# BM83_board.net
KiCad netlist of a schematic drawn in EAGLE
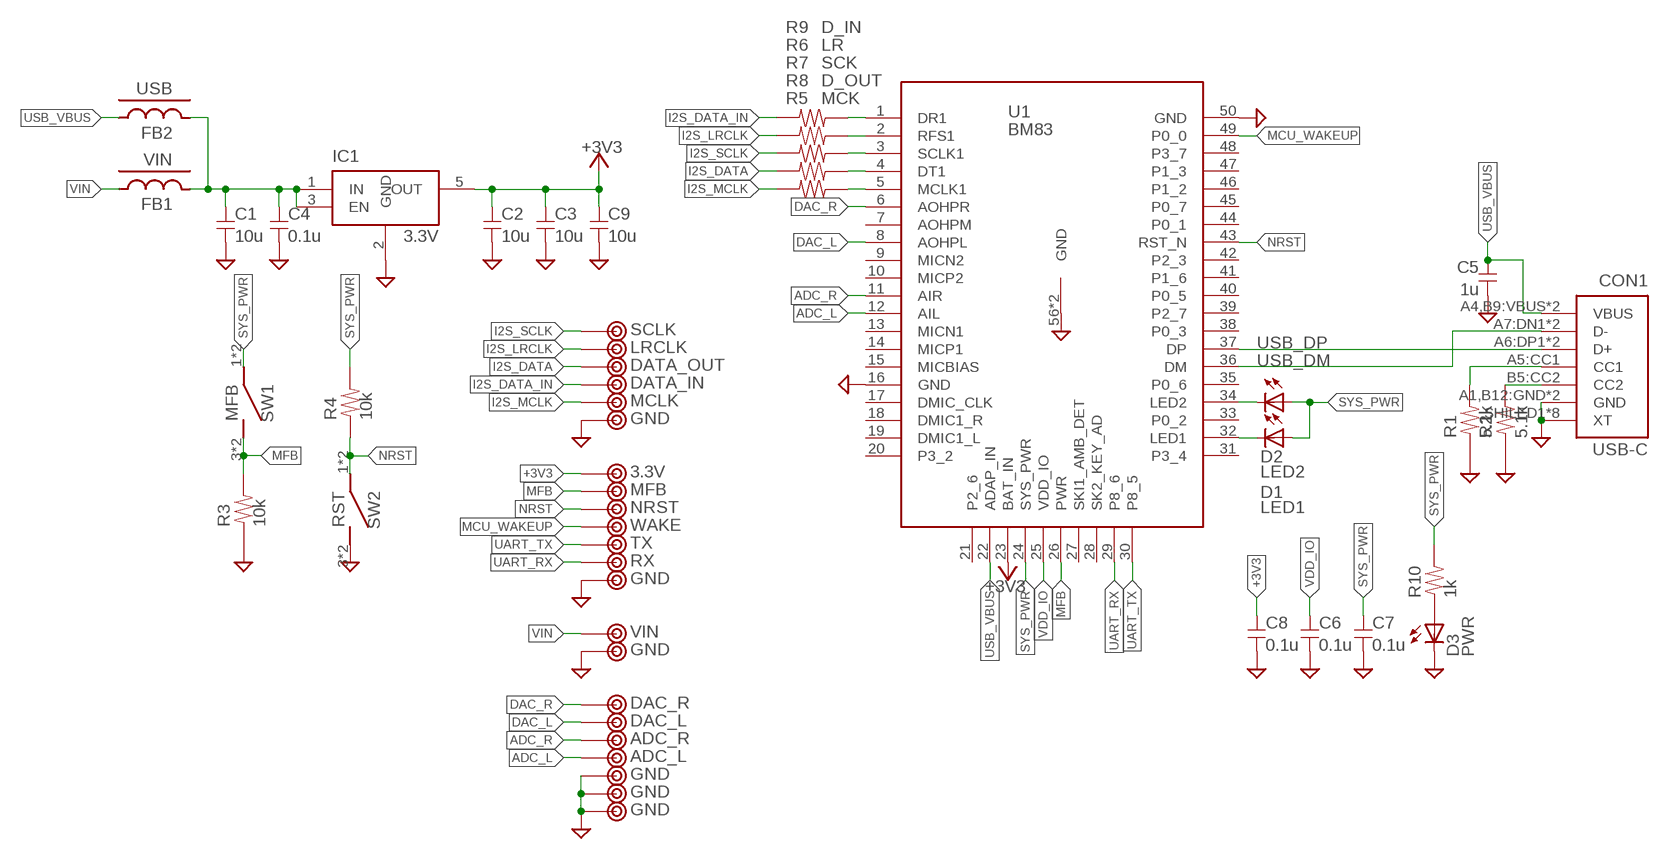
[diagram p0: schematic, sheet 1]

(export (version "E")
  (design (tool "Eeschema 10.0.6"))
  (components
    (comp (ref "C1")
      (value "10u")
      (footprint "eagle-import:2012")
      (libsource (lib "eagle-import") (part "C-2012"))
    )
    (comp (ref "C2")
      (value "10u")
      (footprint "eagle-import:2012")
      (libsource (lib "eagle-import") (part "C-2012"))
    )
    (comp (ref "C3")
      (value "10u")
      (footprint "eagle-import:2012")
      (libsource (lib "eagle-import") (part "C-2012"))
    )
    (comp (ref "C4")
      (value "0.1u")
      (footprint "eagle-import:1608C")
      (libsource (lib "eagle-import") (part "C-1608"))
    )
    (comp (ref "C5")
      (value "1u")
      (footprint "eagle-import:1608C")
      (libsource (lib "eagle-import") (part "C-1608"))
    )
    (comp (ref "C6")
      (value "0.1u")
      (footprint "eagle-import:1608C")
      (libsource (lib "eagle-import") (part "C-1608"))
    )
    (comp (ref "C7")
      (value "0.1u")
      (footprint "eagle-import:1608C")
      (libsource (lib "eagle-import") (part "C-1608"))
    )
    (comp (ref "C8")
      (value "0.1u")
      (footprint "eagle-import:1608C")
      (libsource (lib "eagle-import") (part "C-1608"))
    )
    (comp (ref "C9")
      (value "10u")
      (footprint "eagle-import:2012")
      (libsource (lib "eagle-import") (part "C-2012"))
    )
    (comp (ref "CON1")
      (value "USB-C")
      (footprint "eagle-import:5077CR-16-SMC2-BK-TR")
      (libsource (lib "eagle-import") (part "USB-C"))
    )
    (comp (ref "D1")
      (value "LED1")
      (footprint "eagle-import:D1608")
      (libsource (lib "eagle-import") (part "LED-SMD1608"))
    )
    (comp (ref "D2")
      (value "LED2")
      (footprint "eagle-import:D1608")
      (libsource (lib "eagle-import") (part "LED-SMD1608"))
    )
    (comp (ref "D3")
      (value "PWR")
      (footprint "eagle-import:D1608")
      (libsource (lib "eagle-import") (part "LED-SMD1608"))
    )
    (comp (ref "FB1")
      (value "VIN")
      (footprint "eagle-import:1608-FB")
      (libsource (lib "eagle-import") (part "FB-1608FB"))
    )
    (comp (ref "FB2")
      (value "USB")
      (footprint "eagle-import:1608-FB")
      (libsource (lib "eagle-import") (part "FB-1608FB"))
    )
    (comp (ref "IC1")
      (value "3.3V")
      (footprint "eagle-import:SOT23-5")
      (libsource (lib "eagle-import") (part "TLV740"))
    )
    (comp (ref "R1")
      (value "5.1k")
      (footprint "eagle-import:1608")
      (libsource (lib "eagle-import") (part "R-1608"))
    )
    (comp (ref "R2")
      (value "5.1k")
      (footprint "eagle-import:1608")
      (libsource (lib "eagle-import") (part "R-1608"))
    )
    (comp (ref "R3")
      (value "10k")
      (footprint "eagle-import:1608")
      (libsource (lib "eagle-import") (part "R-1608"))
    )
    (comp (ref "R4")
      (value "10k")
      (footprint "eagle-import:1608")
      (libsource (lib "eagle-import") (part "R-1608"))
    )
    (comp (ref "R5")
      (value "MCK")
      (footprint "eagle-import:1608-2")
      (libsource (lib "eagle-import") (part "R-1608-2"))
    )
    (comp (ref "R6")
      (value "LR")
      (footprint "eagle-import:1608-2")
      (libsource (lib "eagle-import") (part "R-1608-2"))
    )
    (comp (ref "R7")
      (value "SCK")
      (footprint "eagle-import:1608-2")
      (libsource (lib "eagle-import") (part "R-1608-2"))
    )
    (comp (ref "R8")
      (value "D_OUT")
      (footprint "eagle-import:1608-2")
      (libsource (lib "eagle-import") (part "R-1608-2"))
    )
    (comp (ref "R9")
      (value "D_IN")
      (footprint "eagle-import:1608-2")
      (libsource (lib "eagle-import") (part "R-1608-2"))
    )
    (comp (ref "R10")
      (value "1k")
      (footprint "eagle-import:1608")
      (libsource (lib "eagle-import") (part "R-1608"))
    )
    (comp (ref "SW1")
      (value "MFB")
      (footprint "eagle-import:SKRPACE010")
      (libsource (lib "eagle-import") (part "SW-SMD"))
    )
    (comp (ref "SW2")
      (value "RST")
      (footprint "eagle-import:SKRPACE010")
      (libsource (lib "eagle-import") (part "SW-SMD"))
    )
    (comp (ref "TP1")
      (value "DAC_R")
      (footprint "eagle-import:TESTPIN")
      (libsource (lib "eagle-import") (part "TESTPIN"))
    )
    (comp (ref "TP2")
      (value "DAC_L")
      (footprint "eagle-import:TESTPIN")
      (libsource (lib "eagle-import") (part "TESTPIN"))
    )
    (comp (ref "TP3")
      (value "GND")
      (footprint "eagle-import:TESTPIN")
      (libsource (lib "eagle-import") (part "TESTPIN"))
    )
    (comp (ref "TP4")
      (value "SCLK")
      (footprint "eagle-import:TESTPIN")
      (libsource (lib "eagle-import") (part "TESTPIN"))
    )
    (comp (ref "TP5")
      (value "LRCLK")
      (footprint "eagle-import:TESTPIN")
      (libsource (lib "eagle-import") (part "TESTPIN"))
    )
    (comp (ref "TP6")
      (value "DATA_OUT")
      (footprint "eagle-import:TESTPIN")
      (libsource (lib "eagle-import") (part "TESTPIN"))
    )
    (comp (ref "TP7")
      (value "DATA_IN")
      (footprint "eagle-import:TESTPIN")
      (libsource (lib "eagle-import") (part "TESTPIN"))
    )
    (comp (ref "TP8")
      (value "MCLK")
      (footprint "eagle-import:TESTPIN")
      (libsource (lib "eagle-import") (part "TESTPIN"))
    )
    (comp (ref "TP9")
      (value "GND")
      (footprint "eagle-import:TESTPIN")
      (libsource (lib "eagle-import") (part "TESTPIN"))
    )
    (comp (ref "TP10")
      (value "3.3V")
      (footprint "eagle-import:TESTPIN")
      (libsource (lib "eagle-import") (part "TESTPIN"))
    )
    (comp (ref "TP11")
      (value "MFB")
      (footprint "eagle-import:TESTPIN")
      (libsource (lib "eagle-import") (part "TESTPIN"))
    )
    (comp (ref "TP12")
      (value "NRST")
      (footprint "eagle-import:TESTPIN")
      (libsource (lib "eagle-import") (part "TESTPIN"))
    )
    (comp (ref "TP13")
      (value "WAKE")
      (footprint "eagle-import:TESTPIN")
      (libsource (lib "eagle-import") (part "TESTPIN"))
    )
    (comp (ref "TP14")
      (value "TX")
      (footprint "eagle-import:TESTPIN")
      (libsource (lib "eagle-import") (part "TESTPIN"))
    )
    (comp (ref "TP15")
      (value "RX")
      (footprint "eagle-import:TESTPIN")
      (libsource (lib "eagle-import") (part "TESTPIN"))
    )
    (comp (ref "TP16")
      (value "GND")
      (footprint "eagle-import:TESTPIN")
      (libsource (lib "eagle-import") (part "TESTPIN"))
    )
    (comp (ref "TP17")
      (value "VIN")
      (footprint "eagle-import:TESTPIN")
      (libsource (lib "eagle-import") (part "TESTPIN"))
    )
    (comp (ref "TP18")
      (value "GND")
      (footprint "eagle-import:TESTPIN")
      (libsource (lib "eagle-import") (part "TESTPIN"))
    )
    (comp (ref "TP19")
      (value "ADC_R")
      (footprint "eagle-import:TESTPIN")
      (libsource (lib "eagle-import") (part "TESTPIN"))
    )
    (comp (ref "TP20")
      (value "ADC_L")
      (footprint "eagle-import:TESTPIN")
      (libsource (lib "eagle-import") (part "TESTPIN"))
    )
    (comp (ref "TP21")
      (value "GND")
      (footprint "eagle-import:TESTPIN")
      (libsource (lib "eagle-import") (part "TESTPIN"))
    )
    (comp (ref "TP22")
      (value "GND")
      (footprint "eagle-import:TESTPIN")
      (libsource (lib "eagle-import") (part "TESTPIN"))
    )
    (comp (ref "U1")
      (value "BM83")
      (footprint "eagle-import:BM83")
      (libsource (lib "eagle-import") (part "BM83"))
    )
  )
  (nets
    (net (code "1") (name "+3V3") (class "Default")
      (node (ref "C2") (pin "1") (pinfunction "1_1") (pintype "passive"))
      (node (ref "C3") (pin "1") (pinfunction "1_1") (pintype "passive"))
      (node (ref "C8") (pin "1") (pinfunction "1_1") (pintype "passive"))
      (node (ref "C9") (pin "1") (pinfunction "1_1") (pintype "passive"))
      (node (ref "IC1") (pin "5") (pinfunction "OUT_5") (pintype "output"))
      (node (ref "TP10") (pin "1") (pinfunction "1_1") (pintype "passive"))
      (node (ref "U1") (pin "23") (pinfunction "BAT_IN_23") (pintype "bidirectional"))
    )
    (net (code "2") (name "/USB_DM") (class "Default")
      (node (ref "CON1") (pin "A7:DN1") (pinfunction "D-_A7:DN1") (pintype "bidirectional"))
      (node (ref "CON1") (pin "B7:DN2") (pinfunction "D-_B7:DN2") (pintype "bidirectional"))
      (node (ref "U1") (pin "36") (pinfunction "DM_36") (pintype "bidirectional"))
    )
    (net (code "3") (name "/USB_DP") (class "Default")
      (node (ref "CON1") (pin "A6:DP1") (pinfunction "D+_A6:DP1") (pintype "bidirectional"))
      (node (ref "CON1") (pin "B6:DP2") (pinfunction "D+_B6:DP2") (pintype "bidirectional"))
      (node (ref "U1") (pin "37") (pinfunction "DP_37") (pintype "bidirectional"))
    )
    (net (code "4") (name "ADC_L") (class "Default")
      (node (ref "TP20") (pin "1") (pinfunction "1_1") (pintype "passive"))
      (node (ref "U1") (pin "12") (pinfunction "AIL_12") (pintype "bidirectional"))
    )
    (net (code "5") (name "ADC_R") (class "Default")
      (node (ref "TP19") (pin "1") (pinfunction "1_1") (pintype "passive"))
      (node (ref "U1") (pin "11") (pinfunction "AIR_11") (pintype "bidirectional"))
    )
    (net (code "6") (name "DAC_L") (class "Default")
      (node (ref "TP2") (pin "1") (pinfunction "1_1") (pintype "passive"))
      (node (ref "U1") (pin "8") (pinfunction "AOHPL_8") (pintype "bidirectional"))
    )
    (net (code "7") (name "DAC_R") (class "Default")
      (node (ref "TP1") (pin "1") (pinfunction "1_1") (pintype "passive"))
      (node (ref "U1") (pin "6") (pinfunction "AOHPR_6") (pintype "bidirectional"))
    )
    (net (code "8") (name "GND") (class "Default")
      (node (ref "C1") (pin "2") (pinfunction "2_2") (pintype "passive"))
      (node (ref "C2") (pin "2") (pinfunction "2_2") (pintype "passive"))
      (node (ref "C3") (pin "2") (pinfunction "2_2") (pintype "passive"))
      (node (ref "C4") (pin "2") (pinfunction "2_2") (pintype "passive"))
      (node (ref "C5") (pin "2") (pinfunction "2_2") (pintype "passive"))
      (node (ref "C6") (pin "2") (pinfunction "2_2") (pintype "passive"))
      (node (ref "C7") (pin "2") (pinfunction "2_2") (pintype "passive"))
      (node (ref "C8") (pin "2") (pinfunction "2_2") (pintype "passive"))
      (node (ref "C9") (pin "2") (pinfunction "2_2") (pintype "passive"))
      (node (ref "CON1") (pin "A1,B12:GND") (pinfunction "GND_A1,B12:GND") (pintype "bidirectional"))
      (node (ref "CON1") (pin "B1,A12:GND") (pinfunction "GND_B1,A12:GND") (pintype "bidirectional"))
      (node (ref "CON1") (pin "SHILED1") (pinfunction "XT_SHILED1") (pintype "bidirectional"))
      (node (ref "CON1") (pin "SHILED2") (pinfunction "XT_SHILED2") (pintype "bidirectional"))
      (node (ref "CON1") (pin "SHILED3") (pinfunction "XT_SHILED3") (pintype "bidirectional"))
      (node (ref "CON1") (pin "SHILED4") (pinfunction "XT_SHILED4") (pintype "bidirectional"))
      (node (ref "CON1") (pin "SHILED5") (pinfunction "XT_SHILED5") (pintype "bidirectional"))
      (node (ref "CON1") (pin "SHILED6") (pinfunction "XT_SHILED6") (pintype "bidirectional"))
      (node (ref "CON1") (pin "SHILED7") (pinfunction "XT_SHILED7") (pintype "bidirectional"))
      (node (ref "CON1") (pin "SHILED8") (pinfunction "XT_SHILED8") (pintype "bidirectional"))
      (node (ref "D3") (pin "K") (pinfunction "K_K") (pintype "passive"))
      (node (ref "IC1") (pin "2") (pinfunction "GND_2") (pintype "input"))
      (node (ref "R1") (pin "1") (pinfunction "1_1") (pintype "passive"))
      (node (ref "R2") (pin "1") (pinfunction "1_1") (pintype "passive"))
      (node (ref "R3") (pin "1") (pinfunction "1_1") (pintype "passive"))
      (node (ref "SW2") (pin "3") (pinfunction "2_3") (pintype "passive"))
      (node (ref "SW2") (pin "4") (pinfunction "2_4") (pintype "passive"))
      (node (ref "TP16") (pin "1") (pinfunction "1_1") (pintype "passive"))
      (node (ref "TP18") (pin "1") (pinfunction "1_1") (pintype "passive"))
      (node (ref "TP21") (pin "1") (pinfunction "1_1") (pintype "passive"))
      (node (ref "TP22") (pin "1") (pinfunction "1_1") (pintype "passive"))
      (node (ref "TP3") (pin "1") (pinfunction "1_1") (pintype "passive"))
      (node (ref "TP9") (pin "1") (pinfunction "1_1") (pintype "passive"))
      (node (ref "U1") (pin "16") (pinfunction "GND_16") (pintype "bidirectional"))
      (node (ref "U1") (pin "50") (pinfunction "GND_50") (pintype "bidirectional"))
      (node (ref "U1") (pin "56") (pinfunction "GND_56") (pintype "bidirectional"))
      (node (ref "U1") (pin "57") (pinfunction "GND_57") (pintype "bidirectional"))
    )
    (net (code "9") (name "I2S_DATA") (class "Default")
      (node (ref "R8") (pin "1") (pinfunction "1_1") (pintype "passive"))
      (node (ref "TP6") (pin "1") (pinfunction "1_1") (pintype "passive"))
    )
    (net (code "10") (name "I2S_DATA_IN") (class "Default")
      (node (ref "R9") (pin "1") (pinfunction "1_1") (pintype "passive"))
      (node (ref "TP7") (pin "1") (pinfunction "1_1") (pintype "passive"))
    )
    (net (code "11") (name "I2S_LRCLK") (class "Default")
      (node (ref "R6") (pin "1") (pinfunction "1_1") (pintype "passive"))
      (node (ref "TP5") (pin "1") (pinfunction "1_1") (pintype "passive"))
    )
    (net (code "12") (name "I2S_MCLK") (class "Default")
      (node (ref "R5") (pin "1") (pinfunction "1_1") (pintype "passive"))
      (node (ref "TP8") (pin "1") (pinfunction "1_1") (pintype "passive"))
    )
    (net (code "13") (name "I2S_SCLK") (class "Default")
      (node (ref "R7") (pin "1") (pinfunction "1_1") (pintype "passive"))
      (node (ref "TP4") (pin "1") (pinfunction "1_1") (pintype "passive"))
    )
    (net (code "14") (name "MCU_WAKEUP") (class "Default")
      (node (ref "TP13") (pin "1") (pinfunction "1_1") (pintype "passive"))
      (node (ref "U1") (pin "49") (pinfunction "P0_0_49") (pintype "bidirectional"))
    )
    (net (code "15") (name "MFB") (class "Default")
      (node (ref "R3") (pin "2") (pinfunction "2_2") (pintype "passive"))
      (node (ref "SW1") (pin "3") (pinfunction "2_3") (pintype "passive"))
      (node (ref "SW1") (pin "4") (pinfunction "2_4") (pintype "passive"))
      (node (ref "TP11") (pin "1") (pinfunction "1_1") (pintype "passive"))
      (node (ref "U1") (pin "26") (pinfunction "PWR_26") (pintype "bidirectional"))
    )
    (net (code "16") (name "NRST") (class "Default")
      (node (ref "R4") (pin "1") (pinfunction "1_1") (pintype "passive"))
      (node (ref "SW2") (pin "1") (pinfunction "1_1") (pintype "passive"))
      (node (ref "SW2") (pin "2") (pinfunction "1_2") (pintype "passive"))
      (node (ref "TP12") (pin "1") (pinfunction "1_1") (pintype "passive"))
      (node (ref "U1") (pin "43") (pinfunction "RST_N_43") (pintype "bidirectional"))
    )
    (net (code "17") (name "Net-(CON1-CC1)") (class "Default")
      (node (ref "CON1") (pin "A5:CC1") (pinfunction "CC1_A5:CC1") (pintype "bidirectional"))
      (node (ref "R1") (pin "2") (pinfunction "2_2") (pintype "passive"))
    )
    (net (code "18") (name "Net-(CON1-CC2)") (class "Default")
      (node (ref "CON1") (pin "B5:CC2") (pinfunction "CC2_B5:CC2") (pintype "bidirectional"))
      (node (ref "R2") (pin "2") (pinfunction "2_2") (pintype "passive"))
    )
    (net (code "19") (name "Net-(D3-PadA)") (class "Default")
      (node (ref "D3") (pin "A") (pinfunction "A_A") (pintype "passive"))
      (node (ref "R10") (pin "1") (pinfunction "1_1") (pintype "passive"))
    )
    (net (code "20") (name "Net-(IC1-EN)") (class "Default")
      (node (ref "C1") (pin "1") (pinfunction "1_1") (pintype "passive"))
      (node (ref "C4") (pin "1") (pinfunction "1_1") (pintype "passive"))
      (node (ref "FB1") (pin "2") (pinfunction "2_2") (pintype "passive"))
      (node (ref "FB2") (pin "2") (pinfunction "2_2") (pintype "passive"))
      (node (ref "IC1") (pin "1") (pinfunction "IN_1") (pintype "input"))
      (node (ref "IC1") (pin "3") (pinfunction "EN_3") (pintype "input"))
    )
    (net (code "21") (name "Net-(U1-DR1)") (class "Default")
      (node (ref "R9") (pin "2") (pinfunction "2_2") (pintype "passive"))
      (node (ref "U1") (pin "1") (pinfunction "DR1_1") (pintype "bidirectional"))
    )
    (net (code "22") (name "Net-(U1-DT1)") (class "Default")
      (node (ref "R8") (pin "2") (pinfunction "2_2") (pintype "passive"))
      (node (ref "U1") (pin "4") (pinfunction "DT1_4") (pintype "bidirectional"))
    )
    (net (code "23") (name "Net-(U1-LED1)") (class "Default")
      (node (ref "D1") (pin "K") (pinfunction "K_K") (pintype "passive"))
      (node (ref "U1") (pin "32") (pinfunction "LED1_32") (pintype "bidirectional"))
    )
    (net (code "24") (name "Net-(U1-LED2)") (class "Default")
      (node (ref "D2") (pin "K") (pinfunction "K_K") (pintype "passive"))
      (node (ref "U1") (pin "34") (pinfunction "LED2_34") (pintype "bidirectional"))
    )
    (net (code "25") (name "Net-(U1-MCLK1)") (class "Default")
      (node (ref "R5") (pin "2") (pinfunction "2_2") (pintype "passive"))
      (node (ref "U1") (pin "5") (pinfunction "MCLK1_5") (pintype "bidirectional"))
    )
    (net (code "26") (name "Net-(U1-RFS1)") (class "Default")
      (node (ref "R6") (pin "2") (pinfunction "2_2") (pintype "passive"))
      (node (ref "U1") (pin "2") (pinfunction "RFS1_2") (pintype "bidirectional"))
    )
    (net (code "27") (name "Net-(U1-SCLK1)") (class "Default")
      (node (ref "R7") (pin "2") (pinfunction "2_2") (pintype "passive"))
      (node (ref "U1") (pin "3") (pinfunction "SCLK1_3") (pintype "bidirectional"))
    )
    (net (code "28") (name "SYS_PWR") (class "Default")
      (node (ref "C7") (pin "1") (pinfunction "1_1") (pintype "passive"))
      (node (ref "D1") (pin "A") (pinfunction "A_A") (pintype "passive"))
      (node (ref "D2") (pin "A") (pinfunction "A_A") (pintype "passive"))
      (node (ref "R10") (pin "2") (pinfunction "2_2") (pintype "passive"))
      (node (ref "R4") (pin "2") (pinfunction "2_2") (pintype "passive"))
      (node (ref "SW1") (pin "1") (pinfunction "1_1") (pintype "passive"))
      (node (ref "SW1") (pin "2") (pinfunction "1_2") (pintype "passive"))
      (node (ref "U1") (pin "24") (pinfunction "SYS_PWR_24") (pintype "bidirectional"))
    )
    (net (code "29") (name "UART_RX") (class "Default")
      (node (ref "TP15") (pin "1") (pinfunction "1_1") (pintype "passive"))
      (node (ref "U1") (pin "29") (pinfunction "P8_6_29") (pintype "bidirectional"))
    )
    (net (code "30") (name "UART_TX") (class "Default")
      (node (ref "TP14") (pin "1") (pinfunction "1_1") (pintype "passive"))
      (node (ref "U1") (pin "30") (pinfunction "P8_5_30") (pintype "bidirectional"))
    )
    (net (code "31") (name "USB_VBUS") (class "Default")
      (node (ref "C5") (pin "1") (pinfunction "1_1") (pintype "passive"))
      (node (ref "CON1") (pin "A4,B9:VBUS") (pinfunction "VBUS_A4,B9:VBUS") (pintype "output"))
      (node (ref "CON1") (pin "B4,A9:VBUS") (pinfunction "VBUS_B4,A9:VBUS") (pintype "output"))
      (node (ref "FB2") (pin "1") (pinfunction "1_1") (pintype "passive"))
      (node (ref "U1") (pin "22") (pinfunction "ADAP_IN_22") (pintype "bidirectional"))
    )
    (net (code "32") (name "VDD_IO") (class "Default")
      (node (ref "C6") (pin "1") (pinfunction "1_1") (pintype "passive"))
      (node (ref "U1") (pin "25") (pinfunction "VDD_IO_25") (pintype "bidirectional"))
    )
    (net (code "33") (name "VIN") (class "Default")
      (node (ref "FB1") (pin "1") (pinfunction "1_1") (pintype "passive"))
      (node (ref "TP17") (pin "1") (pinfunction "1_1") (pintype "passive"))
    )
    (net (code "34") (name "unconnected-(U1-AOHPM-Pad7)") (class "Default")
      (node (ref "U1") (pin "7") (pinfunction "AOHPM_7") (pintype "bidirectional"))
    )
    (net (code "35") (name "unconnected-(U1-DMIC1_L-Pad19)") (class "Default")
      (node (ref "U1") (pin "19") (pinfunction "DMIC1_L_19") (pintype "bidirectional"))
    )
    (net (code "36") (name "unconnected-(U1-DMIC1_R-Pad18)") (class "Default")
      (node (ref "U1") (pin "18") (pinfunction "DMIC1_R_18") (pintype "bidirectional"))
    )
    (net (code "37") (name "unconnected-(U1-DMIC_CLK-Pad17)") (class "Default")
      (node (ref "U1") (pin "17") (pinfunction "DMIC_CLK_17") (pintype "bidirectional"))
    )
    (net (code "38") (name "unconnected-(U1-MICBIAS-Pad15)") (class "Default")
      (node (ref "U1") (pin "15") (pinfunction "MICBIAS_15") (pintype "bidirectional"))
    )
    (net (code "39") (name "unconnected-(U1-MICN1-Pad13)") (class "Default")
      (node (ref "U1") (pin "13") (pinfunction "MICN1_13") (pintype "bidirectional"))
    )
    (net (code "40") (name "unconnected-(U1-MICN2-Pad9)") (class "Default")
      (node (ref "U1") (pin "9") (pinfunction "MICN2_9") (pintype "bidirectional"))
    )
    (net (code "41") (name "unconnected-(U1-MICP1-Pad14)") (class "Default")
      (node (ref "U1") (pin "14") (pinfunction "MICP1_14") (pintype "bidirectional"))
    )
    (net (code "42") (name "unconnected-(U1-MICP2-Pad10)") (class "Default")
      (node (ref "U1") (pin "10") (pinfunction "MICP2_10") (pintype "bidirectional"))
    )
    (net (code "43") (name "unconnected-(U1-P0_1-Pad44)") (class "Default")
      (node (ref "U1") (pin "44") (pinfunction "P0_1_44") (pintype "bidirectional"))
    )
    (net (code "44") (name "unconnected-(U1-P0_2-Pad33)") (class "Default")
      (node (ref "U1") (pin "33") (pinfunction "P0_2_33") (pintype "bidirectional"))
    )
    (net (code "45") (name "unconnected-(U1-P0_3-Pad38)") (class "Default")
      (node (ref "U1") (pin "38") (pinfunction "P0_3_38") (pintype "bidirectional"))
    )
    (net (code "46") (name "unconnected-(U1-P0_5-Pad40)") (class "Default")
      (node (ref "U1") (pin "40") (pinfunction "P0_5_40") (pintype "bidirectional"))
    )
    (net (code "47") (name "unconnected-(U1-P0_6-Pad35)") (class "Default")
      (node (ref "U1") (pin "35") (pinfunction "P0_6_35") (pintype "bidirectional"))
    )
    (net (code "48") (name "unconnected-(U1-P0_7-Pad45)") (class "Default")
      (node (ref "U1") (pin "45") (pinfunction "P0_7_45") (pintype "bidirectional"))
    )
    (net (code "49") (name "unconnected-(U1-P1_2-Pad46)") (class "Default")
      (node (ref "U1") (pin "46") (pinfunction "P1_2_46") (pintype "bidirectional"))
    )
    (net (code "50") (name "unconnected-(U1-P1_3-Pad47)") (class "Default")
      (node (ref "U1") (pin "47") (pinfunction "P1_3_47") (pintype "bidirectional"))
    )
    (net (code "51") (name "unconnected-(U1-P1_6-Pad41)") (class "Default")
      (node (ref "U1") (pin "41") (pinfunction "P1_6_41") (pintype "bidirectional"))
    )
    (net (code "52") (name "unconnected-(U1-P2_3-Pad42)") (class "Default")
      (node (ref "U1") (pin "42") (pinfunction "P2_3_42") (pintype "bidirectional"))
    )
    (net (code "53") (name "unconnected-(U1-P2_6-Pad21)") (class "Default")
      (node (ref "U1") (pin "21") (pinfunction "P2_6_21") (pintype "bidirectional"))
    )
    (net (code "54") (name "unconnected-(U1-P2_7-Pad39)") (class "Default")
      (node (ref "U1") (pin "39") (pinfunction "P2_7_39") (pintype "bidirectional"))
    )
    (net (code "55") (name "unconnected-(U1-P3_2-Pad20)") (class "Default")
      (node (ref "U1") (pin "20") (pinfunction "P3_2_20") (pintype "bidirectional"))
    )
    (net (code "56") (name "unconnected-(U1-P3_4-Pad31)") (class "Default")
      (node (ref "U1") (pin "31") (pinfunction "P3_4_31") (pintype "bidirectional"))
    )
    (net (code "57") (name "unconnected-(U1-P3_7-Pad48)") (class "Default")
      (node (ref "U1") (pin "48") (pinfunction "P3_7_48") (pintype "bidirectional"))
    )
    (net (code "58") (name "unconnected-(U1-SK2_KEY_AD-Pad28)") (class "Default")
      (node (ref "U1") (pin "28") (pinfunction "SK2_KEY_AD_28") (pintype "bidirectional"))
    )
    (net (code "59") (name "unconnected-(U1-SKI1_AMB_DET-Pad27)") (class "Default")
      (node (ref "U1") (pin "27") (pinfunction "SKI1_AMB_DET_27") (pintype "bidirectional"))
    )
  )
)
